# FPGA_Components.net
KiCad netlist of a schematic drawn in Altium Designer
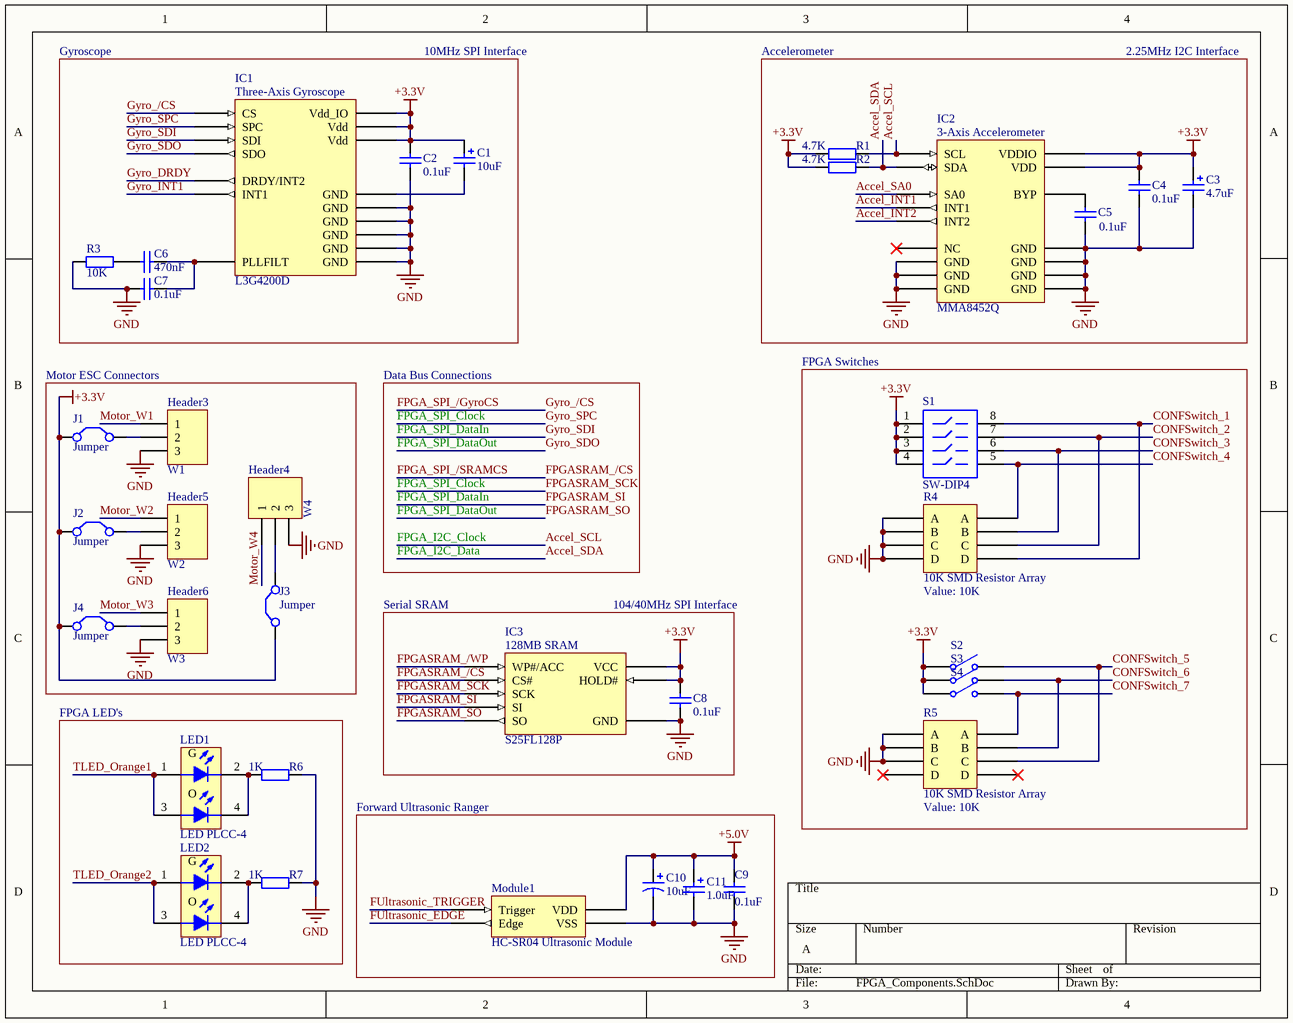
[diagram p0: FPGA_Components.SchDoc]

(export (version "E")
  (design (tool "Eeschema 10.0.6"))
  (components
    (comp (ref "C1")
      (value "10uF")
      (footprint "Capacitor - Tantalum Case A")
      (description "Tantalum Capacitor - Case A")
      (fields (field (name "Comment") "10uF Low-ESR Tantalum CaseA"))
      (libsource (lib "Ad-Flier_Parts") (part "SMD_Cap_Tantalum"))
    )
    (comp (ref "C2")
      (value "0.1uF")
      (footprint "SMD 1206")
      (description "Capacitor")
      (fields (field (name "Comment") "0.1uF SMD 1206"))
      (libsource (lib "Miscellaneous Devices") (part "Cap"))
    )
    (comp (ref "C3")
      (value "4.7uF")
      (footprint "Capacitor - Tantalum Case A")
      (description "Tantalum Capacitor - Case A")
      (fields (field (name "Comment") "4.7uF Low-ESR Tantalum CaseA"))
      (libsource (lib "Ad-Flier_Parts") (part "SMD_Cap_Tantalum"))
    )
    (comp (ref "C4")
      (value "0.1uF")
      (footprint "SMD 1206")
      (description "Capacitor")
      (fields (field (name "Comment") "0.1uF SMD 1206"))
      (libsource (lib "Miscellaneous Devices") (part "Cap"))
    )
    (comp (ref "C5")
      (value "0.1uF")
      (footprint "SMD 1206")
      (description "Capacitor")
      (fields (field (name "Comment") "0.1uF SMD 1206"))
      (libsource (lib "Miscellaneous Devices") (part "Cap"))
    )
    (comp (ref "C6")
      (value "470nF")
      (footprint "SMD 0603")
      (description "Capacitor")
      (fields (field (name "Comment") "470nF SMD 0603"))
      (libsource (lib "Miscellaneous Devices") (part "Cap"))
    )
    (comp (ref "C7")
      (value "0.1uF")
      (footprint "SMD 1206")
      (description "Capacitor")
      (fields (field (name "Comment") "0.1uF SMD 1206"))
      (libsource (lib "Miscellaneous Devices") (part "Cap"))
    )
    (comp (ref "C8")
      (value "0.1uF")
      (footprint "SMD 1206")
      (description "Capacitor")
      (fields (field (name "Comment") "0.1uF SMD 1206"))
      (libsource (lib "Miscellaneous Devices") (part "Cap"))
    )
    (comp (ref "C9")
      (value "0.1uF")
      (footprint "SMD 1206")
      (description "Capacitor")
      (fields (field (name "Comment") "0.1uF SMD 1206"))
      (libsource (lib "Miscellaneous Devices") (part "Cap"))
    )
    (comp (ref "C10")
      (value "10uF")
      (footprint "CAPPR2-5x5")
      (description "Polarized Capacitor (Radial)")
      (fields (field (name "Comment") "10uF Electrolitic") (field (name "PUBLISHER") "Altium Limited"))
      (libsource (lib "Miscellaneous Devices") (part "Cap Pol1"))
    )
    (comp (ref "C11")
      (value "1.0uF")
      (footprint "Capacitor - Tantalum Case A")
      (description "Tantalum Capacitor - Case A")
      (fields (field (name "Comment") "1.0uF Low-ESR Tantalum CaseA"))
      (libsource (lib "Ad-Flier_Parts") (part "SMD_Cap_Tantalum"))
    )
    (comp (ref "Header3")
      (value "W1")
      (footprint "HDR1X3H")
      (description "Header, 3-Pin, Right Angle")
      (fields (field (name "PUBLISHER") "Altium Limited"))
      (libsource (lib "Miscellaneous Connectors") (part "Header 3H"))
    )
    (comp (ref "Header4")
      (value "W4")
      (footprint "HDR1X3H")
      (description "Header, 3-Pin, Right Angle")
      (fields (field (name "PUBLISHER") "Altium Limited"))
      (libsource (lib "") (part "Header 3H_1"))
    )
    (comp (ref "Header5")
      (value "W2")
      (footprint "HDR1X3H")
      (description "Header, 3-Pin, Right Angle")
      (fields (field (name "PUBLISHER") "Altium Limited"))
      (libsource (lib "Miscellaneous Connectors") (part "Header 3H"))
    )
    (comp (ref "Header6")
      (value "W3")
      (footprint "HDR1X3H")
      (description "Header, 3-Pin, Right Angle")
      (fields (field (name "PUBLISHER") "Altium Limited"))
      (libsource (lib "Miscellaneous Connectors") (part "Header 3H"))
    )
    (comp (ref "IC1")
      (value "L3G4200D")
      (footprint "L3G4200DTR")
      (description "Three-Axis Digital Output MEMS Gyroscope")
      (libsource (lib "Ad-Flier_Parts") (part "L3G4200D"))
    )
    (comp (ref "IC2")
      (value "MMA8452Q")
      (footprint "MMA8452QT")
      (description "3-Axis, 12-bit/8-bit Digital Accelerometer")
      (libsource (lib "Ad-Flier_Parts") (part "MMA8452Q"))
    )
    (comp (ref "IC3")
      (value "S25FL128P")
      (footprint "S25FL128P")
      (description "128MB 104-MHz SPI Flash Memory")
      (libsource (lib "Ad-Flier_Parts") (part "S25FL128P"))
    )
    (comp (ref "J1")
      (value "Jumper")
      (footprint "HDR1X2")
      (description "Jumper Wire")
      (fields (field (name "PUBLISHER") "Altium Limited"))
      (libsource (lib "Miscellaneous Devices") (part "Jumper"))
    )
    (comp (ref "J2")
      (value "Jumper")
      (footprint "HDR1X2")
      (description "Jumper Wire")
      (fields (field (name "PUBLISHER") "Altium Limited"))
      (libsource (lib "Miscellaneous Devices") (part "Jumper"))
    )
    (comp (ref "J3")
      (value "Jumper")
      (footprint "HDR1X2")
      (description "Jumper Wire")
      (fields (field (name "PUBLISHER") "Altium Limited"))
      (libsource (lib "Miscellaneous Devices") (part "Jumper"))
    )
    (comp (ref "J4")
      (value "Jumper")
      (footprint "HDR1X2")
      (description "Jumper Wire")
      (fields (field (name "PUBLISHER") "Altium Limited"))
      (libsource (lib "Miscellaneous Devices") (part "Jumper"))
    )
    (comp (ref "LED1")
      (value "LED PLCC-4")
      (footprint "PLCC-4 LED")
      (description "Surface Mount Chip LED")
      (fields (field (name "PUBLISHER") "Altium Limited"))
      (libsource (lib "Avago Optoelectronic LED") (part "LED PLCC-4"))
    )
    (comp (ref "LED2")
      (value "LED PLCC-4")
      (footprint "PLCC-4 LED")
      (description "Surface Mount Chip LED")
      (fields (field (name "PUBLISHER") "Altium Limited"))
      (libsource (lib "Avago Optoelectronic LED") (part "LED PLCC-4"))
    )
    (comp (ref "Module1")
      (value "HC-SR04 Ultrasonic Module")
      (footprint "HC-SR04 Ultrasonic Ranger")
      (libsource (lib "Ad-Flier_Parts") (part "HC-SR04 Ultrasonic Module"))
    )
    (comp (ref "R1")
      (value "4.7K")
      (footprint "SMD 0805")
      (description "Resistor")
      (fields (field (name "Comment") "4.7K SMD 0805"))
      (libsource (lib "Miscellaneous Devices") (part "Res2"))
    )
    (comp (ref "R2")
      (value "4.7K")
      (footprint "SMD 0805")
      (description "Resistor")
      (fields (field (name "Comment") "4.7K SMD 0805"))
      (libsource (lib "") (part "Res2_1"))
    )
    (comp (ref "R3")
      (value "10K")
      (footprint "SMD 0805")
      (description "Resistor")
      (fields (field (name "Comment") "10K SMD 0805"))
      (libsource (lib "Miscellaneous Devices") (part "Res2"))
    )
    (comp (ref "R4")
      (value "10K SMD Resistor Array")
      (footprint "Resistor Array YC164")
      (description "4-Count Resistor Array")
      (fields (field (name "ALTIUM_VALUE") "10K"))
      (libsource (lib "Ad-Flier_Parts") (part "SMD Resistor Array"))
    )
    (comp (ref "R5")
      (value "10K SMD Resistor Array")
      (footprint "Resistor Array YC164")
      (description "4-Count Resistor Array")
      (fields (field (name "ALTIUM_VALUE") "10K"))
      (libsource (lib "Ad-Flier_Parts") (part "SMD Resistor Array"))
    )
    (comp (ref "R6")
      (value "1K")
      (footprint "SMD 0805")
      (description "Resistor")
      (fields (field (name "Comment") "1K SMD 0805"))
      (libsource (lib "") (part "Res2_1"))
    )
    (comp (ref "R7")
      (value "1K")
      (footprint "SMD 0805")
      (description "Resistor")
      (fields (field (name "Comment") "1K SMD 0805"))
      (libsource (lib "") (part "Res2_1"))
    )
    (comp (ref "S1")
      (value "SW-DIP4")
      (footprint "DIP-8")
      (description "DIP Switch")
      (fields (field (name "PUBLISHER") "Altium Limited"))
      (libsource (lib "Miscellaneous Devices") (part "SW-DIP4"))
    )
    (comp (ref "S2")
      (value "SMD Tactile Switch")
      (footprint "SMD Tactile Switch")
      (description "Single-Pole, Single-Throw Switch")
      (fields (field (name "PUBLISHER") "Altium Limited"))
      (libsource (lib "Miscellaneous Devices") (part "SW-SPST"))
    )
    (comp (ref "S3")
      (value "SMD Tactile Switch")
      (footprint "SMD Tactile Switch")
      (description "Single-Pole, Single-Throw Switch")
      (fields (field (name "PUBLISHER") "Altium Limited"))
      (libsource (lib "Miscellaneous Devices") (part "SW-SPST"))
    )
    (comp (ref "S4")
      (value "SMD Tactile Switch")
      (footprint "SMD Tactile Switch")
      (description "Single-Pole, Single-Throw Switch")
      (fields (field (name "PUBLISHER") "Altium Limited"))
      (libsource (lib "Miscellaneous Devices") (part "SW-SPST"))
    )
  )
  (nets
    (net (code "1") (name "+3.3V") (class "Default")
      (node (ref "C1") (pin "1") (pinfunction "+_1") (pintype "passive"))
      (node (ref "C2") (pin "2") (pinfunction "2_2") (pintype "passive"))
      (node (ref "C3") (pin "1") (pinfunction "+_1") (pintype "passive"))
      (node (ref "C4") (pin "1") (pinfunction "1_1") (pintype "passive"))
      (node (ref "C8") (pin "1") (pinfunction "1_1") (pintype "passive"))
      (node (ref "IC1") (pin "0") (pinfunction "Vdd_IO_0") (pintype "power_in"))
      (node (ref "IC1") (pin "14") (pinfunction "Vdd_14") (pintype "power_in"))
      (node (ref "IC1") (pin "15") (pinfunction "Vdd_15") (pintype "power_in"))
      (node (ref "IC2") (pin "0") (pinfunction "VDDIO_0") (pintype "power_in"))
      (node (ref "IC2") (pin "13") (pinfunction "VDD_13") (pintype "power_in"))
      (node (ref "IC3") (pin "6") (pinfunction "HOLD#_6") (pintype "input"))
      (node (ref "IC3") (pin "7") (pinfunction "VCC_7") (pintype "power_in"))
      (node (ref "J1") (pin "1") (pinfunction "C1_1") (pintype "passive"))
      (node (ref "J2") (pin "1") (pinfunction "C1_1") (pintype "passive"))
      (node (ref "J3") (pin "1") (pinfunction "C1_1") (pintype "passive"))
      (node (ref "J4") (pin "1") (pinfunction "C1_1") (pintype "passive"))
      (node (ref "R1") (pin "2") (pinfunction "2_2") (pintype "passive"))
      (node (ref "R2") (pin "1") (pinfunction "1_1") (pintype "passive"))
      (node (ref "S1") (pin "1") (pinfunction "1_1") (pintype "passive"))
      (node (ref "S1") (pin "2") (pinfunction "2_2") (pintype "passive"))
      (node (ref "S1") (pin "3") (pinfunction "3_3") (pintype "passive"))
      (node (ref "S1") (pin "4") (pinfunction "4_4") (pintype "passive"))
      (node (ref "S2") (pin "1") (pinfunction "COMMON_1") (pintype "passive"))
      (node (ref "S3") (pin "1") (pinfunction "COMMON_1") (pintype "passive"))
      (node (ref "S4") (pin "1") (pinfunction "COMMON_1") (pintype "passive"))
    )
    (net (code "2") (name "+5.0V") (class "Default")
      (node (ref "C10") (pin "1") (pinfunction "1_1") (pintype "passive"))
      (node (ref "C11") (pin "1") (pinfunction "+_1") (pintype "passive"))
      (node (ref "C9") (pin "2") (pinfunction "2_2") (pintype "passive"))
      (node (ref "Module1") (pin "0") (pinfunction "VDD_0") (pintype "power_in"))
    )
    (net (code "3") (name "/Accel_INT1") (class "Default")
      (node (ref "IC2") (pin "10") (pinfunction "INT1_10") (pintype "output"))
    )
    (net (code "4") (name "/Accel_INT2") (class "Default")
      (node (ref "IC2") (pin "8") (pinfunction "INT2_8") (pintype "output"))
    )
    (net (code "5") (name "/Accel_SA0") (class "Default")
      (node (ref "IC2") (pin "6") (pinfunction "SA0_6") (pintype "input"))
    )
    (net (code "6") (name "/Accel_SCL") (class "Default")
      (node (ref "IC2") (pin "3") (pinfunction "SCL_3") (pintype "input"))
      (node (ref "R1") (pin "1") (pinfunction "1_1") (pintype "passive"))
    )
    (net (code "7") (name "/Accel_SDA") (class "Default")
      (node (ref "IC2") (pin "5") (pinfunction "SDA_5") (pintype "bidirectional"))
      (node (ref "R2") (pin "2") (pinfunction "2_2") (pintype "passive"))
    )
    (net (code "8") (name "/CONFSwitch_1") (class "Default")
      (node (ref "R4") (pin "4") (pinfunction "D_4") (pintype "passive"))
      (node (ref "S1") (pin "8") (pinfunction "8_8") (pintype "passive"))
    )
    (net (code "9") (name "/CONFSwitch_2") (class "Default")
      (node (ref "R4") (pin "3") (pinfunction "C_3") (pintype "passive"))
      (node (ref "S1") (pin "7") (pinfunction "7_7") (pintype "passive"))
    )
    (net (code "10") (name "/CONFSwitch_3") (class "Default")
      (node (ref "R4") (pin "2") (pinfunction "B_2") (pintype "passive"))
      (node (ref "S1") (pin "6") (pinfunction "6_6") (pintype "passive"))
    )
    (net (code "11") (name "/CONFSwitch_4") (class "Default")
      (node (ref "R4") (pin "1") (pinfunction "A_1") (pintype "passive"))
      (node (ref "S1") (pin "5") (pinfunction "5_5") (pintype "passive"))
    )
    (net (code "12") (name "/CONFSwitch_5") (class "Default")
      (node (ref "R5") (pin "3") (pinfunction "C_3") (pintype "passive"))
      (node (ref "S2") (pin "2") (pinfunction "NO_2") (pintype "passive"))
    )
    (net (code "13") (name "/CONFSwitch_6") (class "Default")
      (node (ref "R5") (pin "2") (pinfunction "B_2") (pintype "passive"))
      (node (ref "S3") (pin "2") (pinfunction "NO_2") (pintype "passive"))
    )
    (net (code "14") (name "/CONFSwitch_7") (class "Default")
      (node (ref "R5") (pin "1") (pinfunction "A_1") (pintype "passive"))
      (node (ref "S4") (pin "2") (pinfunction "NO_2") (pintype "passive"))
    )
    (net (code "15") (name "/FPGASRAM_SCK") (class "Default")
      (node (ref "IC1") (pin "1") (pinfunction "SPC_1") (pintype "input"))
      (node (ref "IC3") (pin "5") (pinfunction "SCK_5") (pintype "input"))
    )
    (net (code "16") (name "/FPGASRAM_SI") (class "Default")
      (node (ref "IC1") (pin "2") (pinfunction "SDI_2") (pintype "input"))
      (node (ref "IC3") (pin "4") (pinfunction "SI_4") (pintype "input"))
    )
    (net (code "17") (name "/FPGASRAM_SO") (class "Default")
      (node (ref "IC1") (pin "3") (pinfunction "SDO_3") (pintype "output"))
      (node (ref "IC3") (pin "1") (pinfunction "SO_1") (pintype "output"))
    )
    (net (code "18") (name "/FPGASRAM_{slash}CS") (class "Default")
      (node (ref "IC3") (pin "0") (pinfunction "CS#_0") (pintype "input"))
    )
    (net (code "19") (name "/FPGASRAM_{slash}WP") (class "Default")
      (node (ref "IC3") (pin "2") (pinfunction "WP#/ACC_2") (pintype "input"))
    )
    (net (code "20") (name "/FPGA_SPI_{slash}GyroCS") (class "Default")
      (node (ref "IC1") (pin "4") (pinfunction "CS_4") (pintype "input"))
    )
    (net (code "21") (name "/FUltrasonic_EDGE") (class "Default")
      (node (ref "Module1") (pin "2") (pinfunction "Edge_2") (pintype "output"))
    )
    (net (code "22") (name "/FUltrasonic_TRIGGER") (class "Default")
      (node (ref "Module1") (pin "1") (pinfunction "Trigger_1") (pintype "input"))
    )
    (net (code "23") (name "/Gyro_DRDY") (class "Default")
      (node (ref "IC1") (pin "5") (pinfunction "DRDY/INT2_5") (pintype "output"))
    )
    (net (code "24") (name "/Gyro_INT1") (class "Default")
      (node (ref "IC1") (pin "6") (pinfunction "INT1_6") (pintype "output"))
    )
    (net (code "25") (name "/Motor_W1") (class "Default")
      (node (ref "Header3") (pin "1") (pinfunction "1_1") (pintype "passive"))
    )
    (net (code "26") (name "/Motor_W2") (class "Default")
      (node (ref "Header5") (pin "1") (pinfunction "1_1") (pintype "passive"))
    )
    (net (code "27") (name "/Motor_W3") (class "Default")
      (node (ref "Header6") (pin "1") (pinfunction "1_1") (pintype "passive"))
    )
    (net (code "28") (name "/Motor_W4") (class "Default")
      (node (ref "Header4") (pin "1") (pinfunction "1_1") (pintype "passive"))
    )
    (net (code "29") (name "/TLED_Orange1") (class "Default")
      (node (ref "LED1") (pin "1") (pinfunction "A1_1") (pintype "passive"))
      (node (ref "LED1") (pin "3") (pinfunction "A2_3") (pintype "passive"))
    )
    (net (code "30") (name "/TLED_Orange2") (class "Default")
      (node (ref "LED2") (pin "1") (pinfunction "A1_1") (pintype "passive"))
      (node (ref "LED2") (pin "3") (pinfunction "A2_3") (pintype "passive"))
    )
    (net (code "31") (name "GND") (class "Default")
      (node (ref "C10") (pin "2") (pinfunction "2_2") (pintype "passive"))
      (node (ref "C11") (pin "2") (pinfunction "-_2") (pintype "passive"))
      (node (ref "C2") (pin "1") (pinfunction "1_1") (pintype "passive"))
      (node (ref "C3") (pin "2") (pinfunction "-_2") (pintype "passive"))
      (node (ref "C4") (pin "2") (pinfunction "2_2") (pintype "passive"))
      (node (ref "C5") (pin "1") (pinfunction "1_1") (pintype "passive"))
      (node (ref "C7") (pin "2") (pinfunction "2_2") (pintype "passive"))
      (node (ref "C8") (pin "2") (pinfunction "2_2") (pintype "passive"))
      (node (ref "C9") (pin "1") (pinfunction "1_1") (pintype "passive"))
      (node (ref "Header3") (pin "3") (pinfunction "3_3") (pintype "passive"))
      (node (ref "Header4") (pin "3") (pinfunction "3_3") (pintype "passive"))
      (node (ref "Header5") (pin "3") (pinfunction "3_3") (pintype "passive"))
      (node (ref "Header6") (pin "3") (pinfunction "3_3") (pintype "passive"))
      (node (ref "IC1") (pin "10") (pinfunction "GND_10") (pintype "power_in"))
      (node (ref "IC1") (pin "11") (pinfunction "GND_11") (pintype "power_in"))
      (node (ref "IC1") (pin "7") (pinfunction "GND_7") (pintype "power_in"))
      (node (ref "IC1") (pin "8") (pinfunction "GND_8") (pintype "power_in"))
      (node (ref "IC1") (pin "9") (pinfunction "GND_9") (pintype "power_in"))
      (node (ref "IC2") (pin "11") (pinfunction "GND_11") (pintype "power_in"))
      (node (ref "IC2") (pin "12") (pinfunction "GND_12") (pintype "power_in"))
      (node (ref "IC2") (pin "14") (pinfunction "GND_14") (pintype "power_in"))
      (node (ref "IC2") (pin "15") (pinfunction "GND_15") (pintype "power_in"))
      (node (ref "IC2") (pin "4") (pinfunction "GND_4") (pintype "power_in"))
      (node (ref "IC2") (pin "7") (pinfunction "GND_7") (pintype "power_in"))
      (node (ref "IC2") (pin "9") (pinfunction "GND_9") (pintype "power_in"))
      (node (ref "IC3") (pin "3") (pinfunction "GND_3") (pintype "power_in"))
      (node (ref "Module1") (pin "3") (pinfunction "VSS_3") (pintype "power_in"))
      (node (ref "R3") (pin "2") (pinfunction "2_2") (pintype "passive"))
      (node (ref "R4") (pin "5") (pinfunction "A_5") (pintype "passive"))
      (node (ref "R4") (pin "6") (pinfunction "B_6") (pintype "passive"))
      (node (ref "R4") (pin "7") (pinfunction "C_7") (pintype "passive"))
      (node (ref "R4") (pin "8") (pinfunction "D_8") (pintype "passive"))
      (node (ref "R5") (pin "5") (pinfunction "A_5") (pintype "passive"))
      (node (ref "R5") (pin "6") (pinfunction "B_6") (pintype "passive"))
      (node (ref "R5") (pin "7") (pinfunction "C_7") (pintype "passive"))
      (node (ref "R6") (pin "2") (pinfunction "2_2") (pintype "passive"))
      (node (ref "R7") (pin "2") (pinfunction "2_2") (pintype "passive"))
    )
    (net (code "32") (name "Net-(C1--)") (class "Default")
      (node (ref "C1") (pin "2") (pinfunction "-_2") (pintype "passive"))
      (node (ref "IC1") (pin "12") (pinfunction "GND_12") (pintype "power_in"))
    )
    (net (code "33") (name "Net-(C6-Pad2)") (class "Default")
      (node (ref "C6") (pin "2") (pinfunction "2_2") (pintype "passive"))
      (node (ref "R3") (pin "1") (pinfunction "1_1") (pintype "passive"))
    )
    (net (code "34") (name "Net-(IC1-PLLFILT)") (class "Default")
      (node (ref "C6") (pin "1") (pinfunction "1_1") (pintype "passive"))
      (node (ref "C7") (pin "1") (pinfunction "1_1") (pintype "passive"))
      (node (ref "IC1") (pin "13") (pinfunction "PLLFILT_13") (pintype "passive"))
    )
    (net (code "35") (name "Net-(IC2-BYP)") (class "Default")
      (node (ref "C5") (pin "2") (pinfunction "2_2") (pintype "passive"))
      (node (ref "IC2") (pin "1") (pinfunction "BYP_1") (pintype "passive"))
    )
    (net (code "36") (name "Net-(J1-C2)") (class "Default")
      (node (ref "Header3") (pin "2") (pinfunction "2_2") (pintype "passive"))
      (node (ref "J1") (pin "2") (pinfunction "C2_2") (pintype "passive"))
    )
    (net (code "37") (name "Net-(J2-C2)") (class "Default")
      (node (ref "Header5") (pin "2") (pinfunction "2_2") (pintype "passive"))
      (node (ref "J2") (pin "2") (pinfunction "C2_2") (pintype "passive"))
    )
    (net (code "38") (name "Net-(J3-C2)") (class "Default")
      (node (ref "Header4") (pin "2") (pinfunction "2_2") (pintype "passive"))
      (node (ref "J3") (pin "2") (pinfunction "C2_2") (pintype "passive"))
    )
    (net (code "39") (name "Net-(J4-C2)") (class "Default")
      (node (ref "Header6") (pin "2") (pinfunction "2_2") (pintype "passive"))
      (node (ref "J4") (pin "2") (pinfunction "C2_2") (pintype "passive"))
    )
    (net (code "40") (name "Net-(LED1-K1)") (class "Default")
      (node (ref "LED1") (pin "2") (pinfunction "K1_2") (pintype "passive"))
      (node (ref "LED1") (pin "4") (pinfunction "K2_4") (pintype "passive"))
      (node (ref "R6") (pin "1") (pinfunction "1_1") (pintype "passive"))
    )
    (net (code "41") (name "Net-(LED2-K1)") (class "Default")
      (node (ref "LED2") (pin "2") (pinfunction "K1_2") (pintype "passive"))
      (node (ref "LED2") (pin "4") (pinfunction "K2_4") (pintype "passive"))
      (node (ref "R7") (pin "1") (pinfunction "1_1") (pintype "passive"))
    )
    (net (code "42") (name "unconnected-(IC2-NC-Pad2)") (class "Default")
      (node (ref "IC2") (pin "2") (pinfunction "NC_2") (pintype "passive+no_connect"))
    )
    (net (code "43") (name "unconnected-(R5-D-Pad4)") (class "Default")
      (node (ref "R5") (pin "4") (pinfunction "D_4") (pintype "passive+no_connect"))
    )
    (net (code "44") (name "unconnected-(R5-D-Pad8)") (class "Default")
      (node (ref "R5") (pin "8") (pinfunction "D_8") (pintype "passive+no_connect"))
    )
  )
)
